# MCU025B_XDS110_Target_Interface.net
KiCad netlist of a schematic drawn in Altium Designer
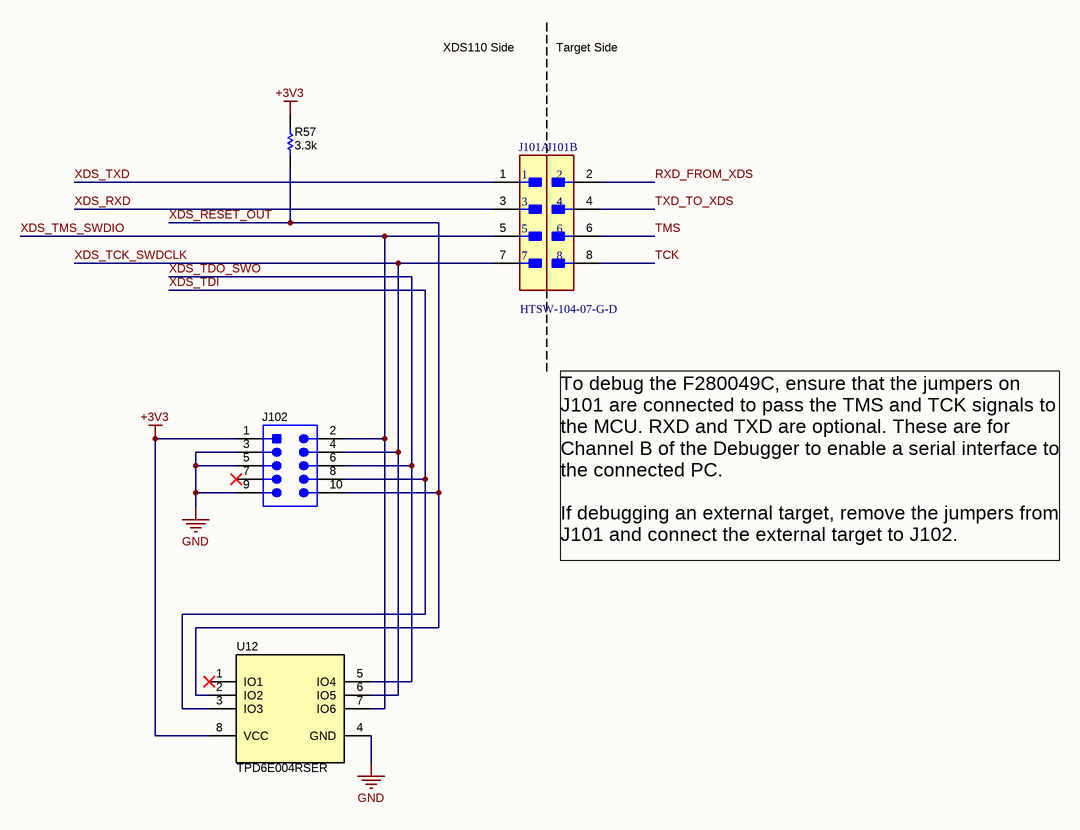
[diagram p0: MCU025B_XDS110_Target_Interface.SchDoc]

(export (version "E")
  (design (tool "Eeschema 10.0.6"))
  (components
    (comp (ref "J101")
      (value "HTSW-104-07-G-D")
      (footprint "FP-HTSW-104-07-G-D-MFG")
      (description "CONN HEADER VERT 8POS 2.54MM")
      (fields
        (field (name "MANUFACTURER") "Samtec")
        (field (name "OCTOPART") "https://octopart.com/htsw-104-07-g-d-samtec-10613822")
      )
      (libsource (lib "Altium Content Vault") (part "811e954b9c034aa737de4d9295cbe7e"))
    )
    (comp (ref "J102")
      (value "FTSH-105-01-F-DV-K")
      (footprint "Samtec_FTSH-105-01-x-DV-K")
      (description "Header (Shrouded), 1.27mm, 5x2, Gold, SMT")
      (fields (field (name "MANUFACTURER") "Samtec") (field (name "PUBLISHER") "Texas Instruments"))
      (libsource (lib "Altium Vault - TI") (part "CMP-0075670-1"))
    )
    (comp (ref "R57")
      (value "CRCW04023K30JNED")
      (footprint "0402")
      (description "RES, 3.3 k, 5%, 0.063 W, AEC-Q200 Grade 0, 0402")
      (fields (field (name "VALUEDISPLAYED") "3.3k") (field (name "MANUFACTURER") "Vishay-Dale"))
      (libsource (lib "Altium Vault - TI") (part "Resistor"))
    )
    (comp (ref "U12")
      (value "TPD6E004RSER")
      (footprint "RSE0008A")
      (fields (field (name "MANUFACTURER") "Texas Instruments"))
      (libsource (lib "Altium Vault - TI") (part "TI-TPD6E004-UQFN_RSE-8"))
    )
  )
  (nets
    (net (code "1") (name "+3V3") (class "Default")
      (node (ref "J102") (pin "1") (pinfunction "1_1") (pintype "passive"))
      (node (ref "R57") (pin "2") (pinfunction "2_2") (pintype "passive"))
      (node (ref "U12") (pin "8") (pinfunction "VCC_8") (pintype "power_in"))
    )
    (net (code "2") (name "/RXD_FROM_XDS") (class "Default")
      (node (ref "J101") (pin "2") (pinfunction "2_2") (pintype "passive"))
    )
    (net (code "3") (name "/TCK") (class "Default")
      (node (ref "J101") (pin "8") (pinfunction "8_8") (pintype "passive"))
    )
    (net (code "4") (name "/TMS") (class "Default")
      (node (ref "J101") (pin "6") (pinfunction "6_6") (pintype "passive"))
    )
    (net (code "5") (name "/TXD_TO_XDS") (class "Default")
      (node (ref "J101") (pin "4") (pinfunction "4_4") (pintype "passive"))
    )
    (net (code "6") (name "/XDS_RESET_OUT") (class "Default")
      (node (ref "J102") (pin "10") (pinfunction "10_10") (pintype "passive"))
      (node (ref "R57") (pin "1") (pinfunction "1_1") (pintype "passive"))
      (node (ref "U12") (pin "2") (pinfunction "IO2_2") (pintype "passive"))
    )
    (net (code "7") (name "/XDS_RXD") (class "Default")
      (node (ref "J101") (pin "3") (pinfunction "3_3") (pintype "passive"))
    )
    (net (code "8") (name "/XDS_TCK_SWDCLK") (class "Default")
      (node (ref "J101") (pin "7") (pinfunction "7_7") (pintype "passive"))
      (node (ref "J102") (pin "4") (pinfunction "4_4") (pintype "passive"))
      (node (ref "U12") (pin "6") (pinfunction "IO5_6") (pintype "passive"))
    )
    (net (code "9") (name "/XDS_TDI") (class "Default")
      (node (ref "J102") (pin "8") (pinfunction "8_8") (pintype "passive"))
      (node (ref "U12") (pin "3") (pinfunction "IO3_3") (pintype "passive"))
    )
    (net (code "10") (name "/XDS_TDO_SWO") (class "Default")
      (node (ref "J102") (pin "6") (pinfunction "6_6") (pintype "passive"))
      (node (ref "U12") (pin "5") (pinfunction "IO4_5") (pintype "passive"))
    )
    (net (code "11") (name "/XDS_TMS_SWDIO") (class "Default")
      (node (ref "J101") (pin "5") (pinfunction "5_5") (pintype "passive"))
      (node (ref "J102") (pin "2") (pinfunction "2_2") (pintype "passive"))
      (node (ref "U12") (pin "7") (pinfunction "IO6_7") (pintype "passive"))
    )
    (net (code "12") (name "/XDS_TXD") (class "Default")
      (node (ref "J101") (pin "1") (pinfunction "1_1") (pintype "passive"))
    )
    (net (code "13") (name "GND") (class "Default")
      (node (ref "J102") (pin "3") (pinfunction "3_3") (pintype "passive"))
      (node (ref "J102") (pin "5") (pinfunction "5_5") (pintype "passive"))
      (node (ref "J102") (pin "9") (pinfunction "9_9") (pintype "passive"))
      (node (ref "U12") (pin "4") (pinfunction "GND_4") (pintype "power_in"))
    )
    (net (code "14") (name "unconnected-(J102-Pad7)") (class "Default")
      (node (ref "J102") (pin "7") (pinfunction "7_7") (pintype "passive+no_connect"))
    )
    (net (code "15") (name "unconnected-(U12-IO1-Pad1)") (class "Default")
      (node (ref "U12") (pin "1") (pinfunction "IO1_1") (pintype "passive+no_connect"))
    )
  )
)
